# 7_RFID_OLED.net
KiCad netlist of a schematic drawn in Altium Designer
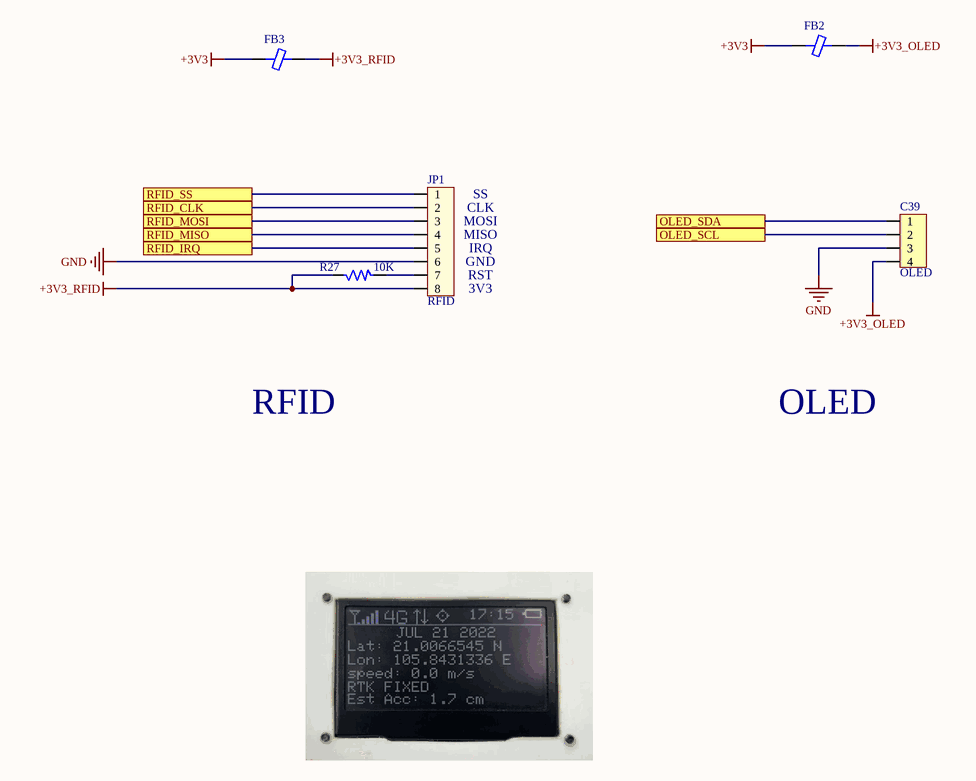
[diagram p0: [7]RFID_OLED.SchDoc]

(export (version "E")
  (design (tool "Eeschema 10.0.6"))
  (components
    (comp (ref "C39")
      (value "OLED")
      (footprint "CON_4P")
      (description "Header IDC, 4 x 1 Pin Vertical 2.54mm Pitch (Non-Boxed, Male)")
      (fields
        (field (name "MANUFACTURER") "Würth Elektronik eiSos GmbH")
        (field (name "PARTNO") "613002143121")
        (field (name "CREATED BY") "Karrer Zheng")
      )
      (libsource (lib "My Library") (part "Header4"))
    )
    (comp (ref "FB2")
      (value "120R")
      (footprint "RES-SMD-0805")
      (description "Ferrite beads")
      (libsource (lib "bla") (part "Ferrite beads"))
    )
    (comp (ref "FB3")
      (value "120R")
      (footprint "RES-SMD-0805")
      (description "Ferrite beads")
      (libsource (lib "bla") (part "Ferrite beads"))
    )
    (comp (ref "JP1")
      (value "RFID")
      (footprint "CON_8P")
      (description "Connector 8")
      (libsource (lib "My Library") (part "Con8"))
    )
    (comp (ref "R27")
      (value "10K")
      (footprint "R0805")
      (description "Resistor SMD")
      (libsource (lib "GPS_Traking_V1_1") (part "RM"))
    )
  )
  (nets
    (net (code "1") (name "+3V3") (class "Default")
      (node (ref "FB2") (pin "1") (pinfunction "1_1") (pintype "passive"))
      (node (ref "FB3") (pin "1") (pinfunction "1_1") (pintype "passive"))
    )
    (net (code "2") (name "+3V3_OLED") (class "Default")
      (node (ref "C39") (pin "4") (pinfunction "4_4") (pintype "passive"))
      (node (ref "FB2") (pin "2") (pinfunction "2_2") (pintype "passive"))
    )
    (net (code "3") (name "+3V3_RFID") (class "Default")
      (node (ref "FB3") (pin "2") (pinfunction "2_2") (pintype "passive"))
      (node (ref "JP1") (pin "8") (pinfunction "8_8") (pintype "passive"))
      (node (ref "R27") (pin "1") (pinfunction "1_1") (pintype "passive"))
    )
    (net (code "4") (name "/OLED_SCL") (class "Default")
      (node (ref "C39") (pin "2") (pinfunction "2_2") (pintype "passive"))
    )
    (net (code "5") (name "/OLED_SDA") (class "Default")
      (node (ref "C39") (pin "1") (pinfunction "1_1") (pintype "passive"))
    )
    (net (code "6") (name "/RFID_CLK") (class "Default")
      (node (ref "JP1") (pin "2") (pinfunction "2_2") (pintype "passive"))
    )
    (net (code "7") (name "/RFID_IRQ") (class "Default")
      (node (ref "JP1") (pin "5") (pinfunction "5_5") (pintype "passive"))
    )
    (net (code "8") (name "/RFID_MISO") (class "Default")
      (node (ref "JP1") (pin "4") (pinfunction "4_4") (pintype "passive"))
    )
    (net (code "9") (name "/RFID_MOSI") (class "Default")
      (node (ref "JP1") (pin "3") (pinfunction "3_3") (pintype "passive"))
    )
    (net (code "10") (name "/RFID_SS") (class "Default")
      (node (ref "JP1") (pin "1") (pinfunction "1_1") (pintype "passive"))
    )
    (net (code "11") (name "GND") (class "Default")
      (node (ref "C39") (pin "3") (pinfunction "3_3") (pintype "passive"))
      (node (ref "JP1") (pin "6") (pinfunction "6_6") (pintype "passive"))
    )
    (net (code "12") (name "Net-(JP1-Pad7)") (class "Default")
      (node (ref "JP1") (pin "7") (pinfunction "7_7") (pintype "passive"))
      (node (ref "R27") (pin "2") (pinfunction "2_2") (pintype "passive"))
    )
  )
)
